# A_INPUT.net
KiCad netlist of a schematic drawn in Altium Designer
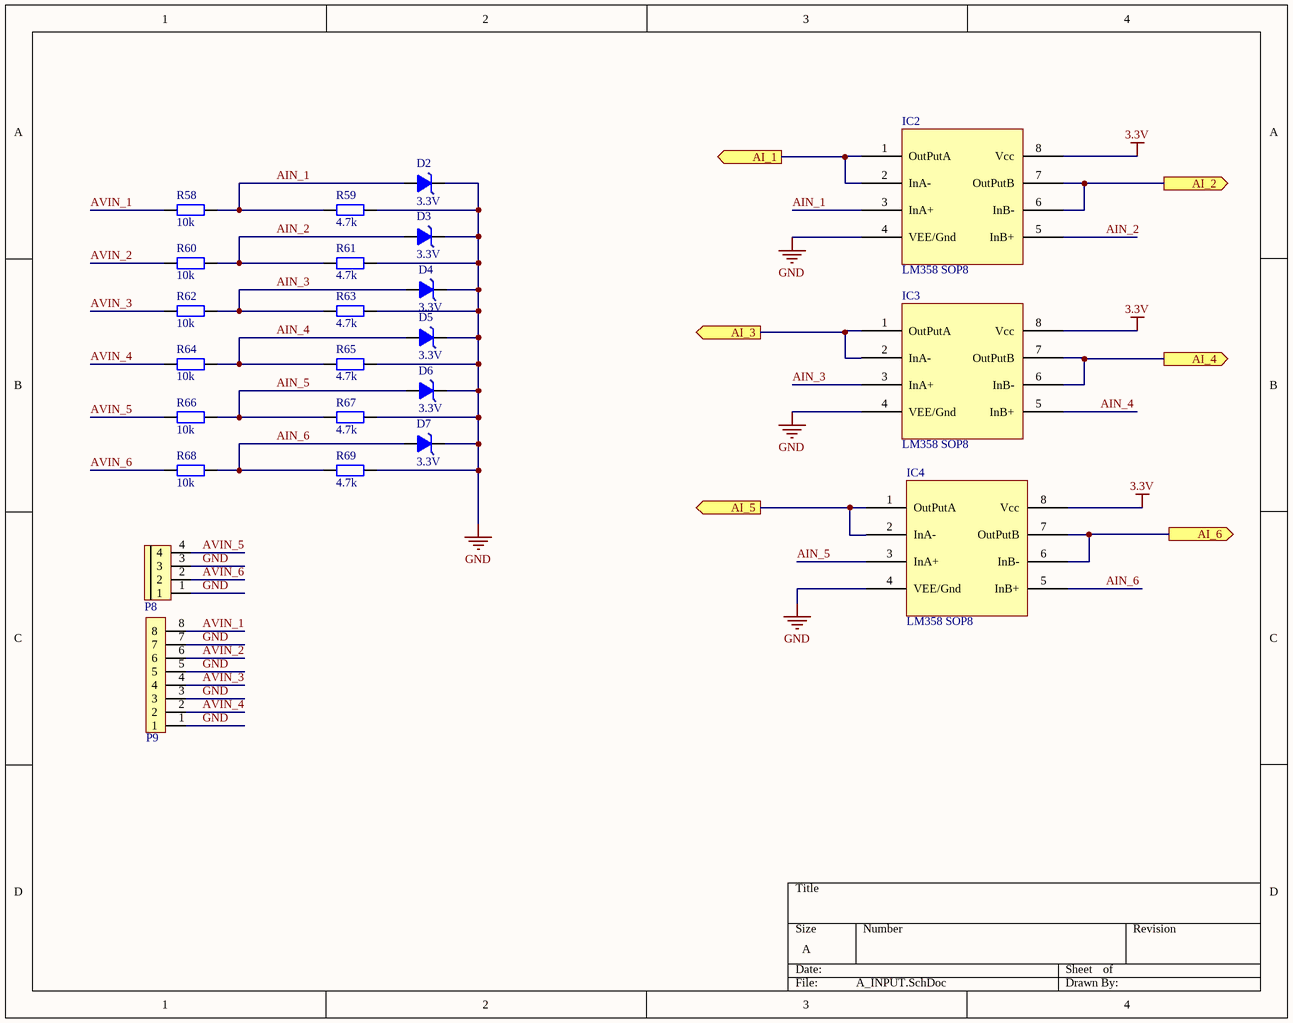
[diagram p0: A_INPUT.SchDoc]

(export (version "E")
  (design (tool "Eeschema 10.0.6"))
  (components
    (comp (ref "D2")
      (value "3.3V")
      (footprint "DIODE ZENNER SMD SOD80")
      (description "Dán")
      (libsource (lib "Altium_Lib_by_KhueNguyenCreator") (part "Diode Zener 3.3V"))
    )
    (comp (ref "D3")
      (value "3.3V")
      (footprint "DIODE ZENNER SMD SOD80")
      (description "Dán")
      (libsource (lib "Altium_Lib_by_KhueNguyenCreator") (part "Diode Zener 3.3V"))
    )
    (comp (ref "D4")
      (value "3.3V")
      (footprint "DIODE ZENNER SMD SOD80")
      (description "Dán")
      (libsource (lib "Altium_Lib_by_KhueNguyenCreator") (part "Diode Zener 3.3V"))
    )
    (comp (ref "D5")
      (value "3.3V")
      (footprint "DIODE ZENNER SMD SOD80")
      (description "Dán")
      (libsource (lib "Altium_Lib_by_KhueNguyenCreator") (part "Diode Zener 3.3V"))
    )
    (comp (ref "D6")
      (value "3.3V")
      (footprint "DIODE ZENNER SMD SOD80")
      (description "Dán")
      (libsource (lib "Altium_Lib_by_KhueNguyenCreator") (part "Diode Zener 3.3V"))
    )
    (comp (ref "D7")
      (value "3.3V")
      (footprint "DIODE ZENNER SMD SOD80")
      (description "Dán")
      (libsource (lib "Altium_Lib_by_KhueNguyenCreator") (part "Diode Zener 3.3V"))
    )
    (comp (ref "IC2")
      (value "LM358 SOP8")
      (footprint "SOP 8")
      (description "Dán")
      (libsource (lib "Altium_Lib_by_KhueNguyenCreator") (part "LM358 SOP8"))
    )
    (comp (ref "IC3")
      (value "LM358 SOP8")
      (footprint "SOP 8")
      (description "Dán")
      (libsource (lib "Altium_Lib_by_KhueNguyenCreator") (part "LM358 SOP8"))
    )
    (comp (ref "IC4")
      (value "LM358 SOP8")
      (footprint "SOP 8")
      (description "Dán")
      (libsource (lib "Altium_Lib_by_KhueNguyenCreator") (part "LM358 SOP8"))
    )
    (comp (ref "P8")
      (value "CON 4 EDG5.08")
      (footprint "CON 4 4EDG5.08")
      (description "Cắm")
      (libsource (lib "Altium_Lib_by_KhueNguyenCreator") (part "CON 4 EDG5.08"))
    )
    (comp (ref "P9")
      (value "CON 8 EDG5.08")
      (footprint "CON 8 8EDG5.08")
      (description "Cắm")
      (libsource (lib "Altium_Lib_by_KhueNguyenCreator") (part "CON 8 EDG5.08"))
    )
    (comp (ref "R58")
      (value "10k")
      (footprint "tro smd 0805")
      (description "Dán")
      (libsource (lib "Altium_Lib_by_KhueNguyenCreator") (part "Tro 0805 5% 10k"))
    )
    (comp (ref "R59")
      (value "4.7k")
      (footprint "tro smd 0805")
      (description "Dán")
      (libsource (lib "Altium_Lib_by_KhueNguyenCreator") (part "Tro 0805 5% 4.7k"))
    )
    (comp (ref "R60")
      (value "10k")
      (footprint "tro smd 0805")
      (description "Dán")
      (libsource (lib "Altium_Lib_by_KhueNguyenCreator") (part "Tro 0805 5% 10k"))
    )
    (comp (ref "R61")
      (value "4.7k")
      (footprint "tro smd 0805")
      (description "Dán")
      (libsource (lib "Altium_Lib_by_KhueNguyenCreator") (part "Tro 0805 5% 4.7k"))
    )
    (comp (ref "R62")
      (value "10k")
      (footprint "tro smd 0805")
      (description "Dán")
      (libsource (lib "Altium_Lib_by_KhueNguyenCreator") (part "Tro 0805 5% 10k"))
    )
    (comp (ref "R63")
      (value "4.7k")
      (footprint "tro smd 0805")
      (description "Dán")
      (libsource (lib "Altium_Lib_by_KhueNguyenCreator") (part "Tro 0805 5% 4.7k"))
    )
    (comp (ref "R64")
      (value "10k")
      (footprint "tro smd 0805")
      (description "Dán")
      (libsource (lib "Altium_Lib_by_KhueNguyenCreator") (part "Tro 0805 5% 10k"))
    )
    (comp (ref "R65")
      (value "4.7k")
      (footprint "tro smd 0805")
      (description "Dán")
      (libsource (lib "Altium_Lib_by_KhueNguyenCreator") (part "Tro 0805 5% 4.7k"))
    )
    (comp (ref "R66")
      (value "10k")
      (footprint "tro smd 0805")
      (description "Dán")
      (libsource (lib "Altium_Lib_by_KhueNguyenCreator") (part "Tro 0805 5% 10k"))
    )
    (comp (ref "R67")
      (value "4.7k")
      (footprint "tro smd 0805")
      (description "Dán")
      (libsource (lib "Altium_Lib_by_KhueNguyenCreator") (part "Tro 0805 5% 4.7k"))
    )
    (comp (ref "R68")
      (value "10k")
      (footprint "tro smd 0805")
      (description "Dán")
      (libsource (lib "Altium_Lib_by_KhueNguyenCreator") (part "Tro 0805 5% 10k"))
    )
    (comp (ref "R69")
      (value "4.7k")
      (footprint "tro smd 0805")
      (description "Dán")
      (libsource (lib "Altium_Lib_by_KhueNguyenCreator") (part "Tro 0805 5% 4.7k"))
    )
  )
  (nets
    (net (code "1") (name "/AIN_1") (class "Default")
      (node (ref "D2") (pin "1") (pinfunction "A_1") (pintype "passive"))
      (node (ref "IC2") (pin "3") (pinfunction "InA+_3") (pintype "passive"))
      (node (ref "R58") (pin "1") (pinfunction "1_1") (pintype "passive"))
      (node (ref "R59") (pin "2") (pinfunction "2_2") (pintype "passive"))
    )
    (net (code "2") (name "/AIN_2") (class "Default")
      (node (ref "D3") (pin "1") (pinfunction "A_1") (pintype "passive"))
      (node (ref "IC2") (pin "5") (pinfunction "InB+_5") (pintype "passive"))
      (node (ref "R60") (pin "1") (pinfunction "1_1") (pintype "passive"))
      (node (ref "R61") (pin "2") (pinfunction "2_2") (pintype "passive"))
    )
    (net (code "3") (name "/AIN_3") (class "Default")
      (node (ref "D4") (pin "1") (pinfunction "A_1") (pintype "passive"))
      (node (ref "IC3") (pin "3") (pinfunction "InA+_3") (pintype "passive"))
      (node (ref "R62") (pin "1") (pinfunction "1_1") (pintype "passive"))
      (node (ref "R63") (pin "2") (pinfunction "2_2") (pintype "passive"))
    )
    (net (code "4") (name "/AIN_4") (class "Default")
      (node (ref "D5") (pin "1") (pinfunction "A_1") (pintype "passive"))
      (node (ref "IC3") (pin "5") (pinfunction "InB+_5") (pintype "passive"))
      (node (ref "R64") (pin "1") (pinfunction "1_1") (pintype "passive"))
      (node (ref "R65") (pin "2") (pinfunction "2_2") (pintype "passive"))
    )
    (net (code "5") (name "/AIN_5") (class "Default")
      (node (ref "D6") (pin "1") (pinfunction "A_1") (pintype "passive"))
      (node (ref "IC4") (pin "3") (pinfunction "InA+_3") (pintype "passive"))
      (node (ref "R66") (pin "1") (pinfunction "1_1") (pintype "passive"))
      (node (ref "R67") (pin "2") (pinfunction "2_2") (pintype "passive"))
    )
    (net (code "6") (name "/AIN_6") (class "Default")
      (node (ref "D7") (pin "1") (pinfunction "A_1") (pintype "passive"))
      (node (ref "IC4") (pin "5") (pinfunction "InB+_5") (pintype "passive"))
      (node (ref "R68") (pin "1") (pinfunction "1_1") (pintype "passive"))
      (node (ref "R69") (pin "2") (pinfunction "2_2") (pintype "passive"))
    )
    (net (code "7") (name "/AI_1") (class "Default")
      (node (ref "IC2") (pin "1") (pinfunction "OutPutA_1") (pintype "passive"))
      (node (ref "IC2") (pin "2") (pinfunction "InA-_2") (pintype "passive"))
    )
    (net (code "8") (name "/AI_2") (class "Default")
      (node (ref "IC2") (pin "6") (pinfunction "InB-_6") (pintype "passive"))
      (node (ref "IC2") (pin "7") (pinfunction "OutPutB_7") (pintype "passive"))
    )
    (net (code "9") (name "/AI_3") (class "Default")
      (node (ref "IC3") (pin "1") (pinfunction "OutPutA_1") (pintype "passive"))
      (node (ref "IC3") (pin "2") (pinfunction "InA-_2") (pintype "passive"))
    )
    (net (code "10") (name "/AI_4") (class "Default")
      (node (ref "IC3") (pin "6") (pinfunction "InB-_6") (pintype "passive"))
      (node (ref "IC3") (pin "7") (pinfunction "OutPutB_7") (pintype "passive"))
    )
    (net (code "11") (name "/AI_5") (class "Default")
      (node (ref "IC4") (pin "1") (pinfunction "OutPutA_1") (pintype "passive"))
      (node (ref "IC4") (pin "2") (pinfunction "InA-_2") (pintype "passive"))
    )
    (net (code "12") (name "/AI_6") (class "Default")
      (node (ref "IC4") (pin "6") (pinfunction "InB-_6") (pintype "passive"))
      (node (ref "IC4") (pin "7") (pinfunction "OutPutB_7") (pintype "passive"))
    )
    (net (code "13") (name "/AVIN_1") (class "Default")
      (node (ref "P9") (pin "8") (pinfunction "8_8") (pintype "passive"))
      (node (ref "R58") (pin "2") (pinfunction "2_2") (pintype "passive"))
    )
    (net (code "14") (name "/AVIN_2") (class "Default")
      (node (ref "P9") (pin "6") (pinfunction "6_6") (pintype "passive"))
      (node (ref "R60") (pin "2") (pinfunction "2_2") (pintype "passive"))
    )
    (net (code "15") (name "/AVIN_3") (class "Default")
      (node (ref "P9") (pin "4") (pinfunction "4_4") (pintype "passive"))
      (node (ref "R62") (pin "2") (pinfunction "2_2") (pintype "passive"))
    )
    (net (code "16") (name "/AVIN_4") (class "Default")
      (node (ref "P9") (pin "2") (pinfunction "2_2") (pintype "passive"))
      (node (ref "R64") (pin "2") (pinfunction "2_2") (pintype "passive"))
    )
    (net (code "17") (name "/AVIN_5") (class "Default")
      (node (ref "P8") (pin "4") (pinfunction "4_4") (pintype "passive"))
      (node (ref "R66") (pin "2") (pinfunction "2_2") (pintype "passive"))
    )
    (net (code "18") (name "/AVIN_6") (class "Default")
      (node (ref "P8") (pin "2") (pinfunction "2_2") (pintype "passive"))
      (node (ref "R68") (pin "2") (pinfunction "2_2") (pintype "passive"))
    )
    (net (code "19") (name "3.3V") (class "Default")
      (node (ref "IC2") (pin "8") (pinfunction "Vcc_8") (pintype "passive"))
      (node (ref "IC3") (pin "8") (pinfunction "Vcc_8") (pintype "passive"))
      (node (ref "IC4") (pin "8") (pinfunction "Vcc_8") (pintype "passive"))
    )
    (net (code "20") (name "GND") (class "Default")
      (node (ref "D2") (pin "2") (pinfunction "K_2") (pintype "passive"))
      (node (ref "D3") (pin "2") (pinfunction "K_2") (pintype "passive"))
      (node (ref "D4") (pin "2") (pinfunction "K_2") (pintype "passive"))
      (node (ref "D5") (pin "2") (pinfunction "K_2") (pintype "passive"))
      (node (ref "D6") (pin "2") (pinfunction "K_2") (pintype "passive"))
      (node (ref "D7") (pin "2") (pinfunction "K_2") (pintype "passive"))
      (node (ref "IC2") (pin "4") (pinfunction "VEE/Gnd_4") (pintype "passive"))
      (node (ref "IC3") (pin "4") (pinfunction "VEE/Gnd_4") (pintype "passive"))
      (node (ref "IC4") (pin "4") (pinfunction "VEE/Gnd_4") (pintype "passive"))
      (node (ref "P8") (pin "1") (pinfunction "1_1") (pintype "passive"))
      (node (ref "P8") (pin "3") (pinfunction "3_3") (pintype "passive"))
      (node (ref "P9") (pin "1") (pinfunction "1_1") (pintype "passive"))
      (node (ref "P9") (pin "3") (pinfunction "3_3") (pintype "passive"))
      (node (ref "P9") (pin "5") (pinfunction "5_5") (pintype "passive"))
      (node (ref "P9") (pin "7") (pinfunction "7_7") (pintype "passive"))
      (node (ref "R59") (pin "1") (pinfunction "1_1") (pintype "passive"))
      (node (ref "R61") (pin "1") (pinfunction "1_1") (pintype "passive"))
      (node (ref "R63") (pin "1") (pinfunction "1_1") (pintype "passive"))
      (node (ref "R65") (pin "1") (pinfunction "1_1") (pintype "passive"))
      (node (ref "R67") (pin "1") (pinfunction "1_1") (pintype "passive"))
      (node (ref "R69") (pin "1") (pinfunction "1_1") (pintype "passive"))
    )
  )
)
